# Discharge.net
KiCad netlist of a schematic drawn in Altium Designer
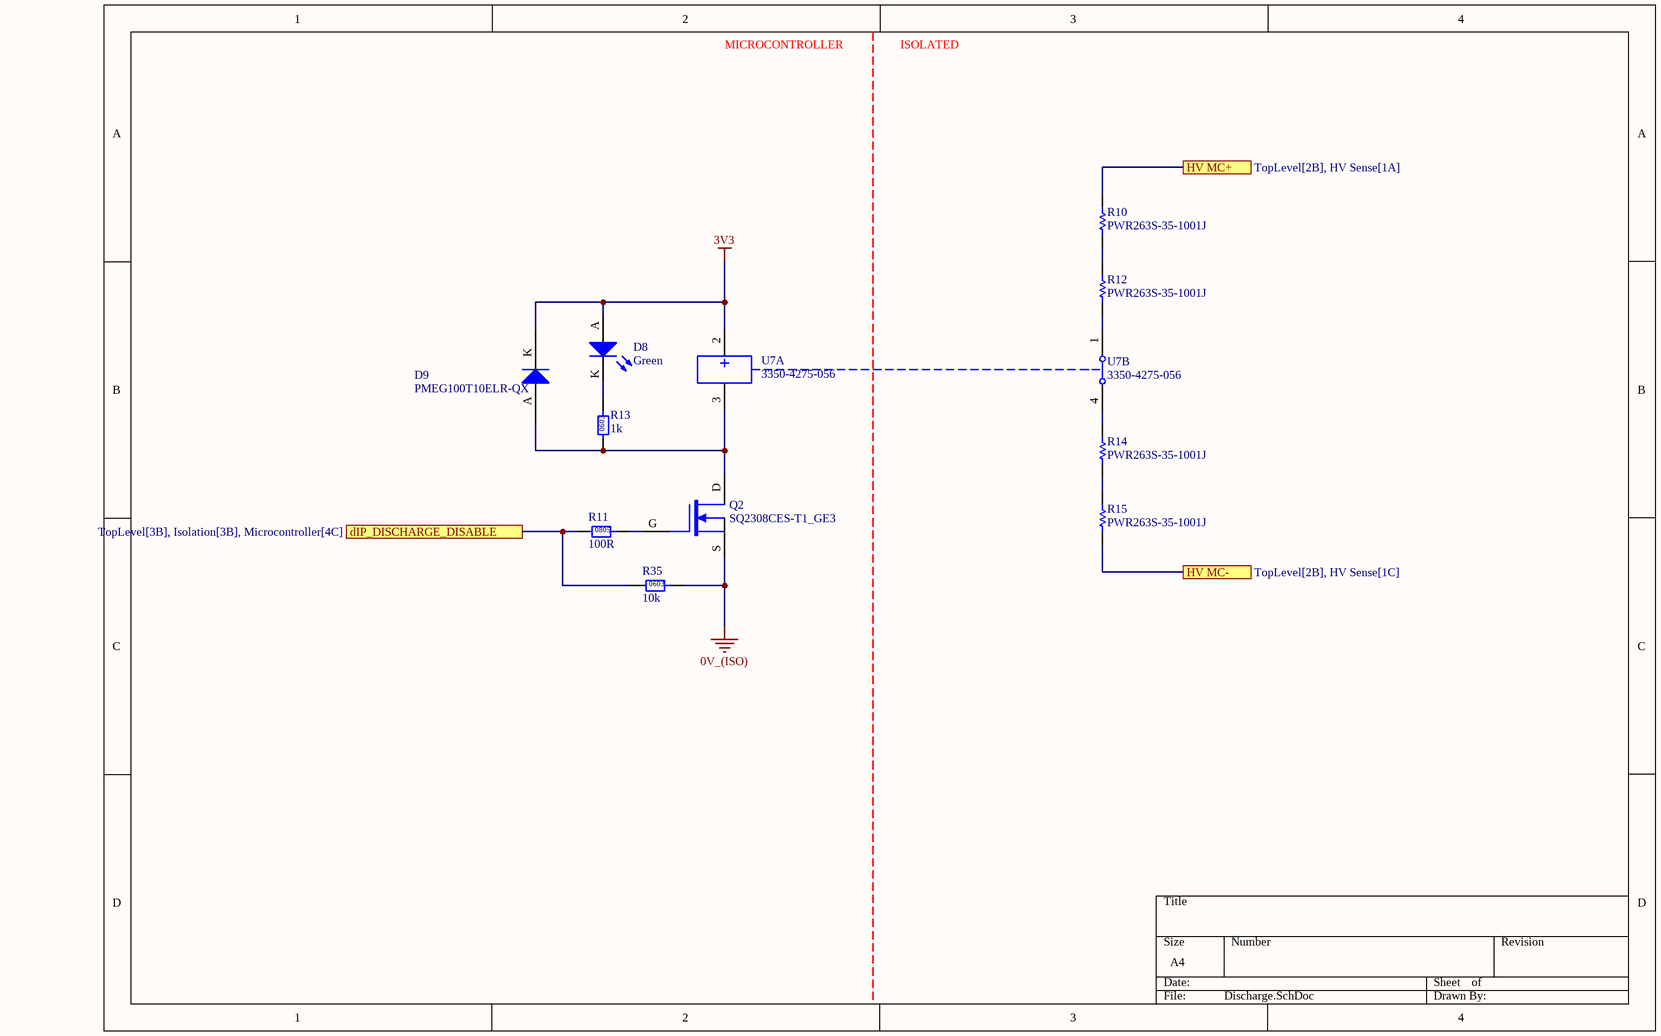
[diagram p0: Discharge.SchDoc]

(export (version "E")
  (design (tool "Eeschema 10.0.6"))
  (components
    (comp (ref "D8")
      (value "Green")
      (footprint "0805 LED")
      (description "Green LED Indication - Discrete 1.75V 0805 (2012 Metric)")
      (fields (field (name "PART NUMBER") "SML-210FTT86") (field (name "MANUFACTURER") "ROHM Semiconductor"))
      (libsource (lib "ts_standard_library") (part "LED"))
    )
    (comp (ref "D9")
      (value "PMEG100T10ELR-QX")
      (footprint "SODFL350X110-2N")
      (description "Diode 100 V 1A Surface Mount SOD-123W")
      (libsource (lib "Team Swinburne") (part "PMEG100T10ELR-QX"))
    )
    (comp (ref "Q2")
      (value "SQ2308CES-T1_GE3")
      (footprint "VSHY SOT-23-3")
      (description "MOSFET N-CH 60V 2.3A SOT23")
      (fields
        (field (name "MANUFACTURER") "Vishay Siliconix")
        (field (name "DIGIKEY PART NUMBER") "SQ2308CES-T1_GE3CT-ND")
        (field (name "PUBLISHER") "Altium Limited")
      )
      (libsource (lib "ts_standard_library") (part "MOSFET-N"))
    )
    (comp (ref "R10")
      (value "PWR263S-35-1001J")
      (footprint "B TO-263")
      (fields
        (field (name "MANUFACTURER") "Bournes Inc")
        (field (name "TOLERANCE") "0.05")
        (field (name "DIGIKEY PART NUMBER") "PWR263S-35-1001J-ND")
      )
      (libsource (lib "Team Swinburne") (part "Resistor"))
    )
    (comp (ref "R11")
      (value "100R")
      (footprint "0805")
      (fields
        (field (name "PART NUMBER") "RC0805FR07100RL")
        (field (name "MANUFACTURER") "YAGEO")
        (field (name "TOLERANCE") "0.01")
      )
      (libsource (lib "ts_standard_library") (part "Resistor 0805"))
    )
    (comp (ref "R12")
      (value "PWR263S-35-1001J")
      (footprint "B TO-263")
      (fields
        (field (name "MANUFACTURER") "Bournes Inc")
        (field (name "TOLERANCE") "0.05")
        (field (name "DIGIKEY PART NUMBER") "PWR263S-35-1001J-ND")
      )
      (libsource (lib "Team Swinburne") (part "Resistor"))
    )
    (comp (ref "R13")
      (value "1k")
      (footprint "0603")
      (fields
        (field (name "PART NUMBER") "RC0603FR-071KL")
        (field (name "MANUFACTURER") "YAGEO")
        (field (name "TOLERANCE") "0.01")
      )
      (libsource (lib "ts_standard_library") (part "Resistor 0603"))
    )
    (comp (ref "R14")
      (value "PWR263S-35-1001J")
      (footprint "B TO-263")
      (fields
        (field (name "MANUFACTURER") "Bournes Inc")
        (field (name "TOLERANCE") "0.05")
        (field (name "DIGIKEY PART NUMBER") "PWR263S-35-1001J-ND")
      )
      (libsource (lib "Team Swinburne") (part "Resistor"))
    )
    (comp (ref "R15")
      (value "PWR263S-35-1001J")
      (footprint "B TO-263")
      (fields
        (field (name "MANUFACTURER") "Bournes Inc")
        (field (name "TOLERANCE") "0.05")
        (field (name "DIGIKEY PART NUMBER") "PWR263S-35-1001J-ND")
      )
      (libsource (lib "Team Swinburne") (part "Resistor"))
    )
    (comp (ref "R35")
      (value "10k")
      (footprint "0603")
      (fields
        (field (name "PART NUMBER") "RC0603FR-0710KL")
        (field (name "MANUFACTURER") "YAGEO")
        (field (name "TOLERANCE") "0.01")
      )
      (libsource (lib "ts_standard_library") (part "Resistor 0603"))
    )
    (comp (ref "U7")
      (value "3350-4275-056")
      (footprint "CI SPST")
      (description "RELAY REED HV SPST 200W 3A 5V (NC)")
      (libsource (lib "Team Swinburne") (part "3350-4275-056"))
    )
  )
  (nets
    (net (code "1") (name "/HV MC+") (class "Default")
      (node (ref "R10") (pin "1") (pinfunction "1_1") (pintype "passive"))
    )
    (net (code "2") (name "/HV MC-") (class "Default")
      (node (ref "R15") (pin "2") (pinfunction "2_2") (pintype "passive"))
    )
    (net (code "3") (name "/dIP_DISCHARGE_DISABLE") (class "Default")
      (node (ref "R11") (pin "1") (pinfunction "1_1") (pintype "passive"))
      (node (ref "R35") (pin "1") (pinfunction "1_1") (pintype "passive"))
    )
    (net (code "4") (name "0V_(ISO)") (class "Default")
      (node (ref "Q2") (pin "S") (pinfunction "S_S") (pintype "passive"))
      (node (ref "R35") (pin "2") (pinfunction "2_2") (pintype "passive"))
    )
    (net (code "5") (name "3V3") (class "Default")
      (node (ref "D8") (pin "A") (pinfunction "A_A") (pintype "passive"))
      (node (ref "D9") (pin "K") (pintype "passive"))
      (node (ref "U7") (pin "2") (pinfunction "2_2") (pintype "passive"))
    )
    (net (code "6") (name "Net-(D8-PadK)") (class "Default")
      (node (ref "D8") (pin "K") (pinfunction "K_K") (pintype "passive"))
      (node (ref "R13") (pin "2") (pinfunction "2_2") (pintype "passive"))
    )
    (net (code "7") (name "Net-(D9-PadA)") (class "Default")
      (node (ref "D9") (pin "A") (pintype "passive"))
      (node (ref "Q2") (pin "D") (pinfunction "D_D") (pintype "passive"))
      (node (ref "R13") (pin "1") (pinfunction "1_1") (pintype "passive"))
      (node (ref "U7") (pin "3") (pinfunction "3_3") (pintype "passive"))
    )
    (net (code "8") (name "Net-(Q2-PadG)") (class "Default")
      (node (ref "Q2") (pin "G") (pinfunction "G_G") (pintype "passive"))
      (node (ref "R11") (pin "2") (pinfunction "2_2") (pintype "passive"))
    )
    (net (code "9") (name "Net-(R10-Pad2)") (class "Default")
      (node (ref "R10") (pin "2") (pinfunction "2_2") (pintype "passive"))
      (node (ref "R12") (pin "1") (pinfunction "1_1") (pintype "passive"))
    )
    (net (code "10") (name "Net-(R12-Pad2)") (class "Default")
      (node (ref "R12") (pin "2") (pinfunction "2_2") (pintype "passive"))
      (node (ref "U7") (pin "1") (pinfunction "1_1") (pintype "passive"))
    )
    (net (code "11") (name "Net-(R14-Pad1)") (class "Default")
      (node (ref "R14") (pin "1") (pinfunction "1_1") (pintype "passive"))
      (node (ref "U7") (pin "4") (pinfunction "4_4") (pintype "passive"))
    )
    (net (code "12") (name "Net-(R14-Pad2)") (class "Default")
      (node (ref "R14") (pin "2") (pinfunction "2_2") (pintype "passive"))
      (node (ref "R15") (pin "1") (pinfunction "1_1") (pintype "passive"))
    )
  )
)
